# amp_tone_control_v_1_0.net
KiCad netlist of a schematic drawn in EAGLE
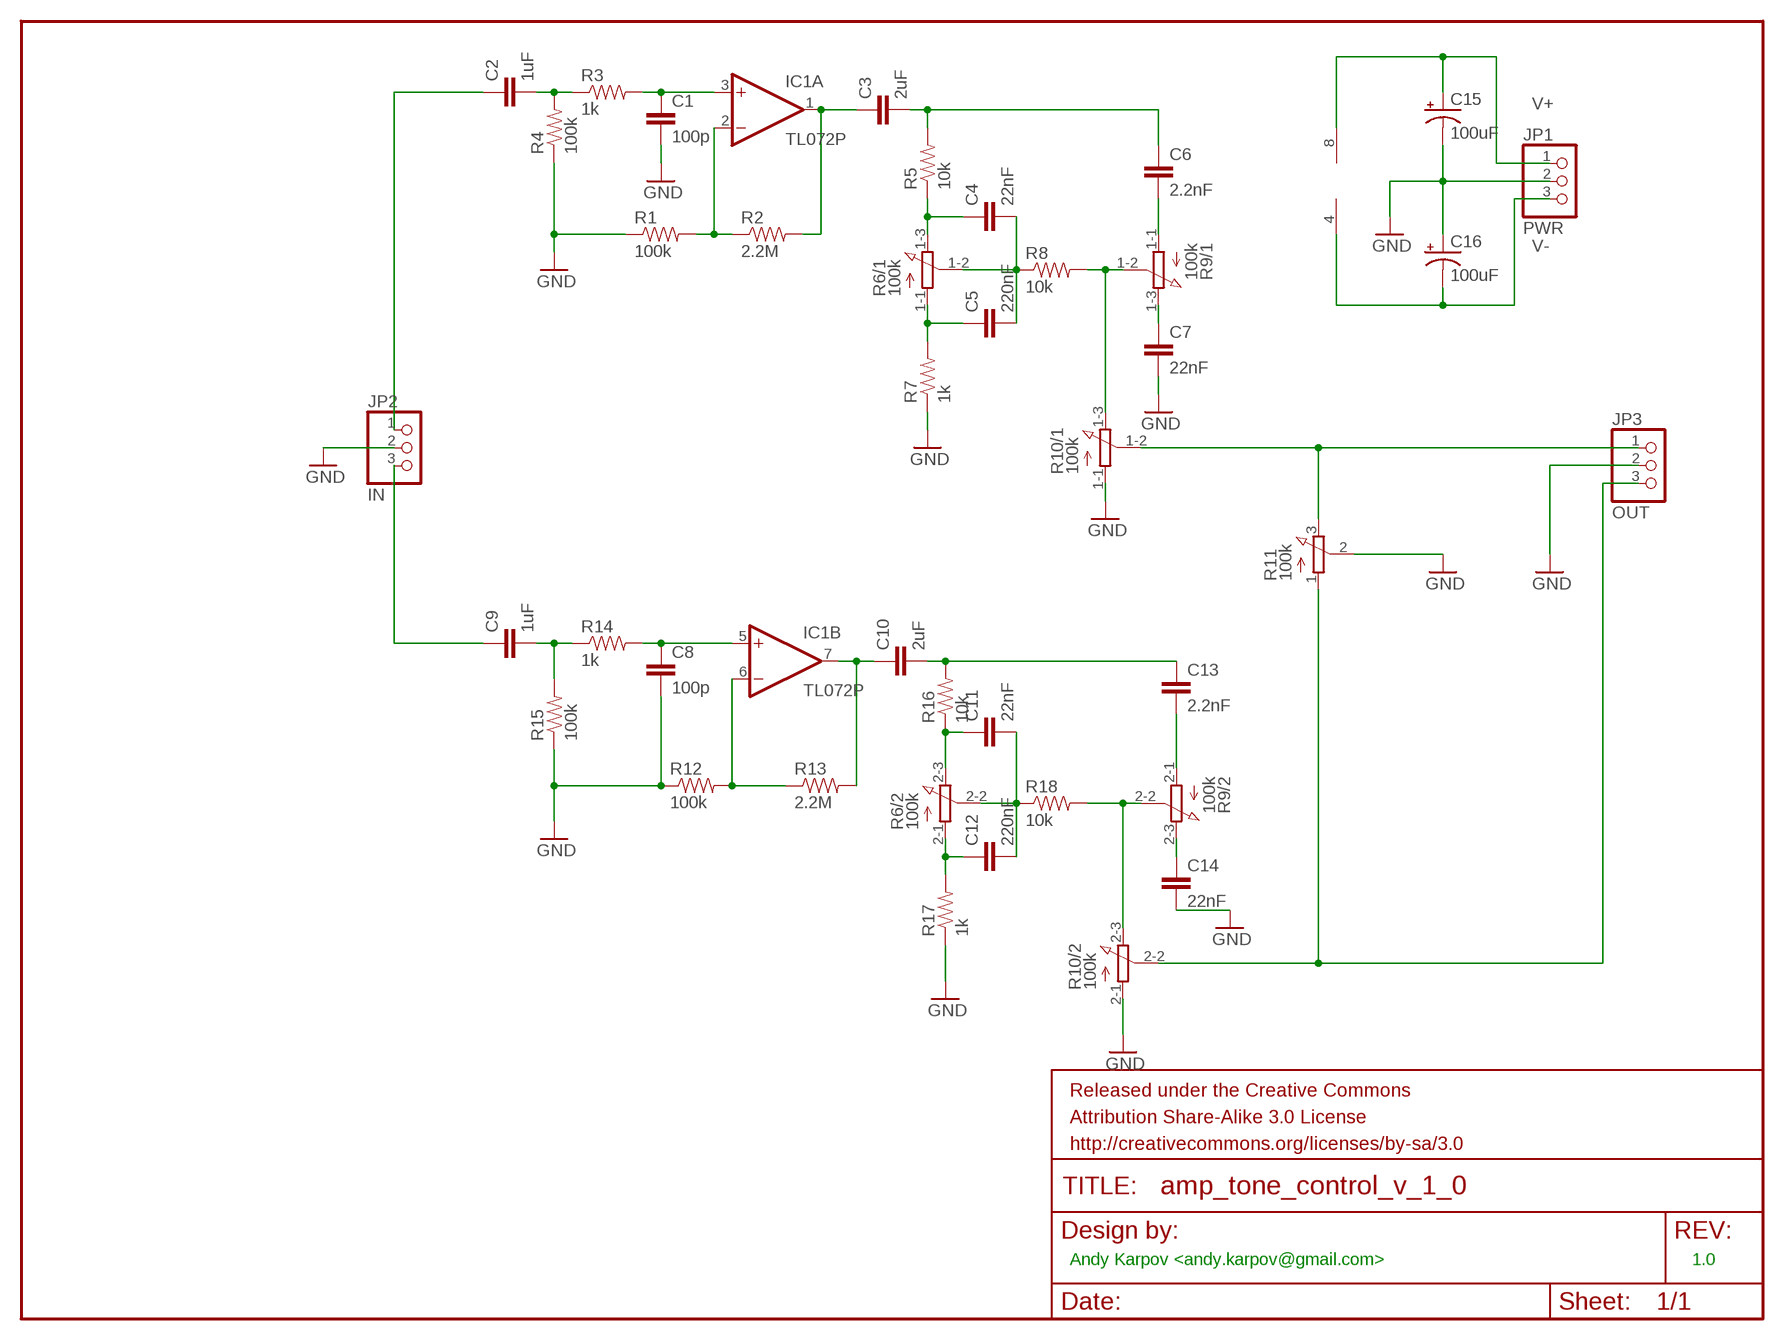
[diagram p0: schematic, sheet 1]

(export (version "E")
  (design (tool "Eeschema 10.0.6"))
  (components
    (comp (ref "C1")
      (value "100p")
      (footprint "eagle-import:CAP-PTH-5MM")
      (libsource (lib "eagle-import") (part "CAPPTH1"))
    )
    (comp (ref "C2")
      (value "1uF")
      (footprint "eagle-import:CAP-PTH-LARGE")
      (libsource (lib "eagle-import") (part "CAPPTH3"))
    )
    (comp (ref "C3")
      (value "2uF")
      (footprint "eagle-import:CAP-PTH-LARGE")
      (libsource (lib "eagle-import") (part "CAPPTH3"))
    )
    (comp (ref "C4")
      (value "22nF")
      (footprint "eagle-import:CAP-PTH-5MM")
      (libsource (lib "eagle-import") (part "CAPPTH1"))
    )
    (comp (ref "C5")
      (value "220nF")
      (footprint "eagle-import:CAP-PTH-5MM")
      (libsource (lib "eagle-import") (part "CAPPTH1"))
    )
    (comp (ref "C6")
      (value "2.2nF")
      (footprint "eagle-import:CAP-PTH-5MM")
      (libsource (lib "eagle-import") (part "CAPPTH1"))
    )
    (comp (ref "C7")
      (value "22nF")
      (footprint "eagle-import:CAP-PTH-LARGE")
      (libsource (lib "eagle-import") (part "CAPPTH3"))
    )
    (comp (ref "C8")
      (value "100p")
      (footprint "eagle-import:CAP-PTH-5MM")
      (libsource (lib "eagle-import") (part "CAPPTH1"))
    )
    (comp (ref "C9")
      (value "1uF")
      (footprint "eagle-import:CAP-PTH-LARGE")
      (libsource (lib "eagle-import") (part "CAPPTH3"))
    )
    (comp (ref "C10")
      (value "2uF")
      (footprint "eagle-import:CAP-PTH-LARGE")
      (libsource (lib "eagle-import") (part "CAPPTH3"))
    )
    (comp (ref "C11")
      (value "22nF")
      (footprint "eagle-import:CAP-PTH-5MM")
      (libsource (lib "eagle-import") (part "CAPPTH1"))
    )
    (comp (ref "C12")
      (value "220nF")
      (footprint "eagle-import:CAP-PTH-5MM")
      (libsource (lib "eagle-import") (part "CAPPTH1"))
    )
    (comp (ref "C13")
      (value "2.2nF")
      (footprint "eagle-import:CAP-PTH-5MM")
      (libsource (lib "eagle-import") (part "CAPPTH1"))
    )
    (comp (ref "C14")
      (value "22nF")
      (footprint "eagle-import:CAP-PTH-LARGE")
      (libsource (lib "eagle-import") (part "CAPPTH3"))
    )
    (comp (ref "C15")
      (value "100uF")
      (footprint "eagle-import:CPOL-RADIAL-100UF-25V")
      (libsource (lib "eagle-import") (part "CAP_POLPTH1"))
    )
    (comp (ref "C16")
      (value "100uF")
      (footprint "eagle-import:CPOL-RADIAL-100UF-25V")
      (libsource (lib "eagle-import") (part "CAP_POLPTH1"))
    )
    (comp (ref "FRAME1")
      (value "FRAME-LETTER")
      (footprint "eagle-import:CREATIVE_COMMONS")
      (libsource (lib "eagle-import") (part "FRAME-LETTER"))
    )
    (comp (ref "IC1")
      (value "TL072P")
      (footprint "eagle-import:DIL08")
      (libsource (lib "eagle-import") (part "TL072P"))
    )
    (comp (ref "JP1")
      (value "PWR")
      (footprint "eagle-import:1X03")
      (libsource (lib "eagle-import") (part "PINHD-1X3"))
    )
    (comp (ref "JP2")
      (value "IN")
      (footprint "eagle-import:1X03")
      (libsource (lib "eagle-import") (part "PINHD-1X3"))
    )
    (comp (ref "JP3")
      (value "OUT")
      (footprint "eagle-import:1X03")
      (libsource (lib "eagle-import") (part "PINHD-1X3"))
    )
    (comp (ref "R1")
      (value "100k")
      (footprint "eagle-import:AXIAL-0.4")
      (libsource (lib "eagle-import") (part "RESISTORPTH-1/4W"))
    )
    (comp (ref "R2")
      (value "2.2M")
      (footprint "eagle-import:AXIAL-0.4")
      (libsource (lib "eagle-import") (part "RESISTORPTH-1/4W"))
    )
    (comp (ref "R3")
      (value "1k")
      (footprint "eagle-import:AXIAL-0.4")
      (libsource (lib "eagle-import") (part "RESISTORPTH-1/4W"))
    )
    (comp (ref "R4")
      (value "100k")
      (footprint "eagle-import:AXIAL-0.4")
      (libsource (lib "eagle-import") (part "RESISTORPTH-1/4W"))
    )
    (comp (ref "R5")
      (value "10k")
      (footprint "eagle-import:AXIAL-0.4")
      (libsource (lib "eagle-import") (part "RESISTORPTH-1/4W"))
    )
    (comp (ref "R6")
      (value "100k")
      (footprint "eagle-import:3RP_1610G")
      (libsource (lib "eagle-import") (part "3RP/1610G"))
    )
    (comp (ref "R7")
      (value "1k")
      (footprint "eagle-import:AXIAL-0.4")
      (libsource (lib "eagle-import") (part "RESISTORPTH-1/4W"))
    )
    (comp (ref "R8")
      (value "10k")
      (footprint "eagle-import:AXIAL-0.4")
      (libsource (lib "eagle-import") (part "RESISTORPTH-1/4W"))
    )
    (comp (ref "R9")
      (value "100k")
      (footprint "eagle-import:3RP_1610G")
      (libsource (lib "eagle-import") (part "3RP/1610G"))
    )
    (comp (ref "R10")
      (value "100k")
      (footprint "eagle-import:3RP_1610G")
      (libsource (lib "eagle-import") (part "3RP/1610G"))
    )
    (comp (ref "R11")
      (value "100k")
      (footprint "eagle-import:3RP_1610N")
      (libsource (lib "eagle-import") (part "3RP/1610N"))
    )
    (comp (ref "R12")
      (value "100k")
      (footprint "eagle-import:AXIAL-0.4")
      (libsource (lib "eagle-import") (part "RESISTORPTH-1/4W"))
    )
    (comp (ref "R13")
      (value "2.2M")
      (footprint "eagle-import:AXIAL-0.4")
      (libsource (lib "eagle-import") (part "RESISTORPTH-1/4W"))
    )
    (comp (ref "R14")
      (value "1k")
      (footprint "eagle-import:AXIAL-0.4")
      (libsource (lib "eagle-import") (part "RESISTORPTH-1/4W"))
    )
    (comp (ref "R15")
      (value "100k")
      (footprint "eagle-import:AXIAL-0.4")
      (libsource (lib "eagle-import") (part "RESISTORPTH-1/4W"))
    )
    (comp (ref "R16")
      (value "10k")
      (footprint "eagle-import:AXIAL-0.4")
      (libsource (lib "eagle-import") (part "RESISTORPTH-1/4W"))
    )
    (comp (ref "R17")
      (value "1k")
      (footprint "eagle-import:AXIAL-0.4")
      (libsource (lib "eagle-import") (part "RESISTORPTH-1/4W"))
    )
    (comp (ref "R18")
      (value "10k")
      (footprint "eagle-import:AXIAL-0.4")
      (libsource (lib "eagle-import") (part "RESISTORPTH-1/4W"))
    )
  )
  (nets
    (net (code "1") (name "/V+") (class "Default")
      (node (ref "C15") (pin "1") (pinfunction "+_1") (pintype "passive"))
      (node (ref "IC1") (pin "8") (pinfunction "V+_8") (pintype "power_in"))
      (node (ref "JP1") (pin "1") (pinfunction "1_1") (pintype "passive"))
    )
    (net (code "2") (name "/V-") (class "Default")
      (node (ref "C16") (pin "2") (pinfunction "-_2") (pintype "passive"))
      (node (ref "IC1") (pin "4") (pinfunction "V-_4") (pintype "power_in"))
      (node (ref "JP1") (pin "3") (pinfunction "3_3") (pintype "passive"))
    )
    (net (code "3") (name "GND") (class "Default")
      (node (ref "C1") (pin "2") (pinfunction "2_2") (pintype "passive"))
      (node (ref "C14") (pin "2") (pinfunction "2_2") (pintype "passive"))
      (node (ref "C15") (pin "2") (pinfunction "-_2") (pintype "passive"))
      (node (ref "C16") (pin "1") (pinfunction "+_1") (pintype "passive"))
      (node (ref "C7") (pin "2") (pinfunction "2_2") (pintype "passive"))
      (node (ref "C8") (pin "2") (pinfunction "2_2") (pintype "passive"))
      (node (ref "JP1") (pin "2") (pinfunction "2_2") (pintype "passive"))
      (node (ref "JP2") (pin "2") (pinfunction "2_2") (pintype "passive"))
      (node (ref "JP3") (pin "2") (pinfunction "2_2") (pintype "passive"))
      (node (ref "R1") (pin "P$1") (pinfunction "1_P$1") (pintype "passive"))
      (node (ref "R10") (pin "1-1") (pinfunction "A_1-1") (pintype "passive"))
      (node (ref "R10") (pin "2-1") (pinfunction "A_2-1") (pintype "passive"))
      (node (ref "R11") (pin "2") (pinfunction "S_2") (pintype "passive"))
      (node (ref "R12") (pin "P$1") (pinfunction "1_P$1") (pintype "passive"))
      (node (ref "R15") (pin "P$1") (pinfunction "1_P$1") (pintype "passive"))
      (node (ref "R17") (pin "P$1") (pinfunction "1_P$1") (pintype "passive"))
      (node (ref "R4") (pin "P$1") (pinfunction "1_P$1") (pintype "passive"))
      (node (ref "R7") (pin "P$1") (pinfunction "1_P$1") (pintype "passive"))
    )
    (net (code "4") (name "Net-(C2-Pad1)") (class "Default")
      (node (ref "C2") (pin "1") (pinfunction "1_1") (pintype "passive"))
      (node (ref "JP2") (pin "1") (pinfunction "1_1") (pintype "passive"))
    )
    (net (code "5") (name "Net-(C9-Pad1)") (class "Default")
      (node (ref "C9") (pin "1") (pinfunction "1_1") (pintype "passive"))
      (node (ref "JP2") (pin "3") (pinfunction "3_3") (pintype "passive"))
    )
    (net (code "6") (name "Net-(IC1A-+IN)") (class "Default")
      (node (ref "C1") (pin "1") (pinfunction "1_1") (pintype "passive"))
      (node (ref "IC1") (pin "3") (pinfunction "+IN_3") (pintype "input"))
      (node (ref "R3") (pin "P$2") (pinfunction "2_P$2") (pintype "passive"))
    )
    (net (code "7") (name "Net-(IC1A--IN)") (class "Default")
      (node (ref "IC1") (pin "2") (pinfunction "-IN_2") (pintype "input"))
      (node (ref "R1") (pin "P$2") (pinfunction "2_P$2") (pintype "passive"))
      (node (ref "R2") (pin "P$1") (pinfunction "1_P$1") (pintype "passive"))
    )
    (net (code "8") (name "Net-(IC1A-OUT)") (class "Default")
      (node (ref "C3") (pin "1") (pinfunction "1_1") (pintype "passive"))
      (node (ref "IC1") (pin "1") (pinfunction "OUT_1") (pintype "output"))
      (node (ref "R2") (pin "P$2") (pinfunction "2_P$2") (pintype "passive"))
    )
    (net (code "9") (name "Net-(IC1B-+IN)") (class "Default")
      (node (ref "C8") (pin "1") (pinfunction "1_1") (pintype "passive"))
      (node (ref "IC1") (pin "5") (pinfunction "+IN_5") (pintype "input"))
      (node (ref "R14") (pin "P$2") (pinfunction "2_P$2") (pintype "passive"))
    )
    (net (code "10") (name "Net-(IC1B--IN)") (class "Default")
      (node (ref "IC1") (pin "6") (pinfunction "-IN_6") (pintype "input"))
      (node (ref "R12") (pin "P$2") (pinfunction "2_P$2") (pintype "passive"))
      (node (ref "R13") (pin "P$1") (pinfunction "1_P$1") (pintype "passive"))
    )
    (net (code "11") (name "Net-(IC1B-OUT)") (class "Default")
      (node (ref "C10") (pin "1") (pinfunction "1_1") (pintype "passive"))
      (node (ref "IC1") (pin "7") (pinfunction "OUT_7") (pintype "output"))
      (node (ref "R13") (pin "P$2") (pinfunction "2_P$2") (pintype "passive"))
    )
    (net (code "12") (name "Net-(R3-1)") (class "Default")
      (node (ref "C2") (pin "2") (pinfunction "2_2") (pintype "passive"))
      (node (ref "R3") (pin "P$1") (pinfunction "1_P$1") (pintype "passive"))
      (node (ref "R4") (pin "P$2") (pinfunction "2_P$2") (pintype "passive"))
    )
    (net (code "13") (name "Net-(R5-1)") (class "Default")
      (node (ref "C4") (pin "1") (pinfunction "1_1") (pintype "passive"))
      (node (ref "R5") (pin "P$1") (pinfunction "1_P$1") (pintype "passive"))
      (node (ref "R6") (pin "1-3") (pinfunction "E_1-3") (pintype "passive"))
    )
    (net (code "14") (name "Net-(R5-2)") (class "Default")
      (node (ref "C3") (pin "2") (pinfunction "2_2") (pintype "passive"))
      (node (ref "C6") (pin "1") (pinfunction "1_1") (pintype "passive"))
      (node (ref "R5") (pin "P$2") (pinfunction "2_P$2") (pintype "passive"))
    )
    (net (code "15") (name "Net-(R6A-A)") (class "Default")
      (node (ref "C5") (pin "1") (pinfunction "1_1") (pintype "passive"))
      (node (ref "R6") (pin "1-1") (pinfunction "A_1-1") (pintype "passive"))
      (node (ref "R7") (pin "P$2") (pinfunction "2_P$2") (pintype "passive"))
    )
    (net (code "16") (name "Net-(R6A-S)") (class "Default")
      (node (ref "C4") (pin "2") (pinfunction "2_2") (pintype "passive"))
      (node (ref "C5") (pin "2") (pinfunction "2_2") (pintype "passive"))
      (node (ref "R6") (pin "1-2") (pinfunction "S_1-2") (pintype "passive"))
      (node (ref "R8") (pin "P$1") (pinfunction "1_P$1") (pintype "passive"))
    )
    (net (code "17") (name "Net-(R9A-A)") (class "Default")
      (node (ref "C6") (pin "2") (pinfunction "2_2") (pintype "passive"))
      (node (ref "R9") (pin "1-1") (pinfunction "A_1-1") (pintype "passive"))
    )
    (net (code "18") (name "Net-(R9A-E)") (class "Default")
      (node (ref "C7") (pin "1") (pinfunction "1_1") (pintype "passive"))
      (node (ref "R9") (pin "1-3") (pinfunction "E_1-3") (pintype "passive"))
    )
    (net (code "19") (name "Net-(R9B-A)") (class "Default")
      (node (ref "C13") (pin "2") (pinfunction "2_2") (pintype "passive"))
      (node (ref "R9") (pin "2-1") (pinfunction "A_2-1") (pintype "passive"))
    )
    (net (code "20") (name "Net-(R9B-E)") (class "Default")
      (node (ref "C14") (pin "1") (pinfunction "1_1") (pintype "passive"))
      (node (ref "R9") (pin "2-3") (pinfunction "E_2-3") (pintype "passive"))
    )
    (net (code "21") (name "Net-(R10A-E)") (class "Default")
      (node (ref "R10") (pin "1-3") (pinfunction "E_1-3") (pintype "passive"))
      (node (ref "R8") (pin "P$2") (pinfunction "2_P$2") (pintype "passive"))
      (node (ref "R9") (pin "1-2") (pinfunction "S_1-2") (pintype "passive"))
    )
    (net (code "22") (name "Net-(R10A-S)") (class "Default")
      (node (ref "JP3") (pin "1") (pinfunction "1_1") (pintype "passive"))
      (node (ref "R10") (pin "1-2") (pinfunction "S_1-2") (pintype "passive"))
      (node (ref "R11") (pin "3") (pinfunction "E_3") (pintype "passive"))
    )
    (net (code "23") (name "Net-(R10B-E)") (class "Default")
      (node (ref "R10") (pin "2-3") (pinfunction "E_2-3") (pintype "passive"))
      (node (ref "R18") (pin "P$2") (pinfunction "2_P$2") (pintype "passive"))
      (node (ref "R9") (pin "2-2") (pinfunction "S_2-2") (pintype "passive"))
    )
    (net (code "24") (name "Net-(R10B-S)") (class "Default")
      (node (ref "JP3") (pin "3") (pinfunction "3_3") (pintype "passive"))
      (node (ref "R10") (pin "2-2") (pinfunction "S_2-2") (pintype "passive"))
      (node (ref "R11") (pin "1") (pinfunction "A_1") (pintype "passive"))
    )
    (net (code "25") (name "Net-(R14-1)") (class "Default")
      (node (ref "C9") (pin "2") (pinfunction "2_2") (pintype "passive"))
      (node (ref "R14") (pin "P$1") (pinfunction "1_P$1") (pintype "passive"))
      (node (ref "R15") (pin "P$2") (pinfunction "2_P$2") (pintype "passive"))
    )
    (net (code "26") (name "Net-(R16-1)") (class "Default")
      (node (ref "C11") (pin "1") (pinfunction "1_1") (pintype "passive"))
      (node (ref "R16") (pin "P$1") (pinfunction "1_P$1") (pintype "passive"))
      (node (ref "R6") (pin "2-3") (pinfunction "E_2-3") (pintype "passive"))
    )
    (net (code "27") (name "Net-(R16-2)") (class "Default")
      (node (ref "C10") (pin "2") (pinfunction "2_2") (pintype "passive"))
      (node (ref "C13") (pin "1") (pinfunction "1_1") (pintype "passive"))
      (node (ref "R16") (pin "P$2") (pinfunction "2_P$2") (pintype "passive"))
    )
    (net (code "28") (name "Net-(R17-2)") (class "Default")
      (node (ref "C12") (pin "1") (pinfunction "1_1") (pintype "passive"))
      (node (ref "R17") (pin "P$2") (pinfunction "2_P$2") (pintype "passive"))
      (node (ref "R6") (pin "2-1") (pinfunction "A_2-1") (pintype "passive"))
    )
    (net (code "29") (name "Net-(R18-1)") (class "Default")
      (node (ref "C11") (pin "2") (pinfunction "2_2") (pintype "passive"))
      (node (ref "C12") (pin "2") (pinfunction "2_2") (pintype "passive"))
      (node (ref "R18") (pin "P$1") (pinfunction "1_P$1") (pintype "passive"))
      (node (ref "R6") (pin "2-2") (pinfunction "S_2-2") (pintype "passive"))
    )
  )
)
